# Vcc.net
KiCad netlist of a schematic drawn in EAGLE
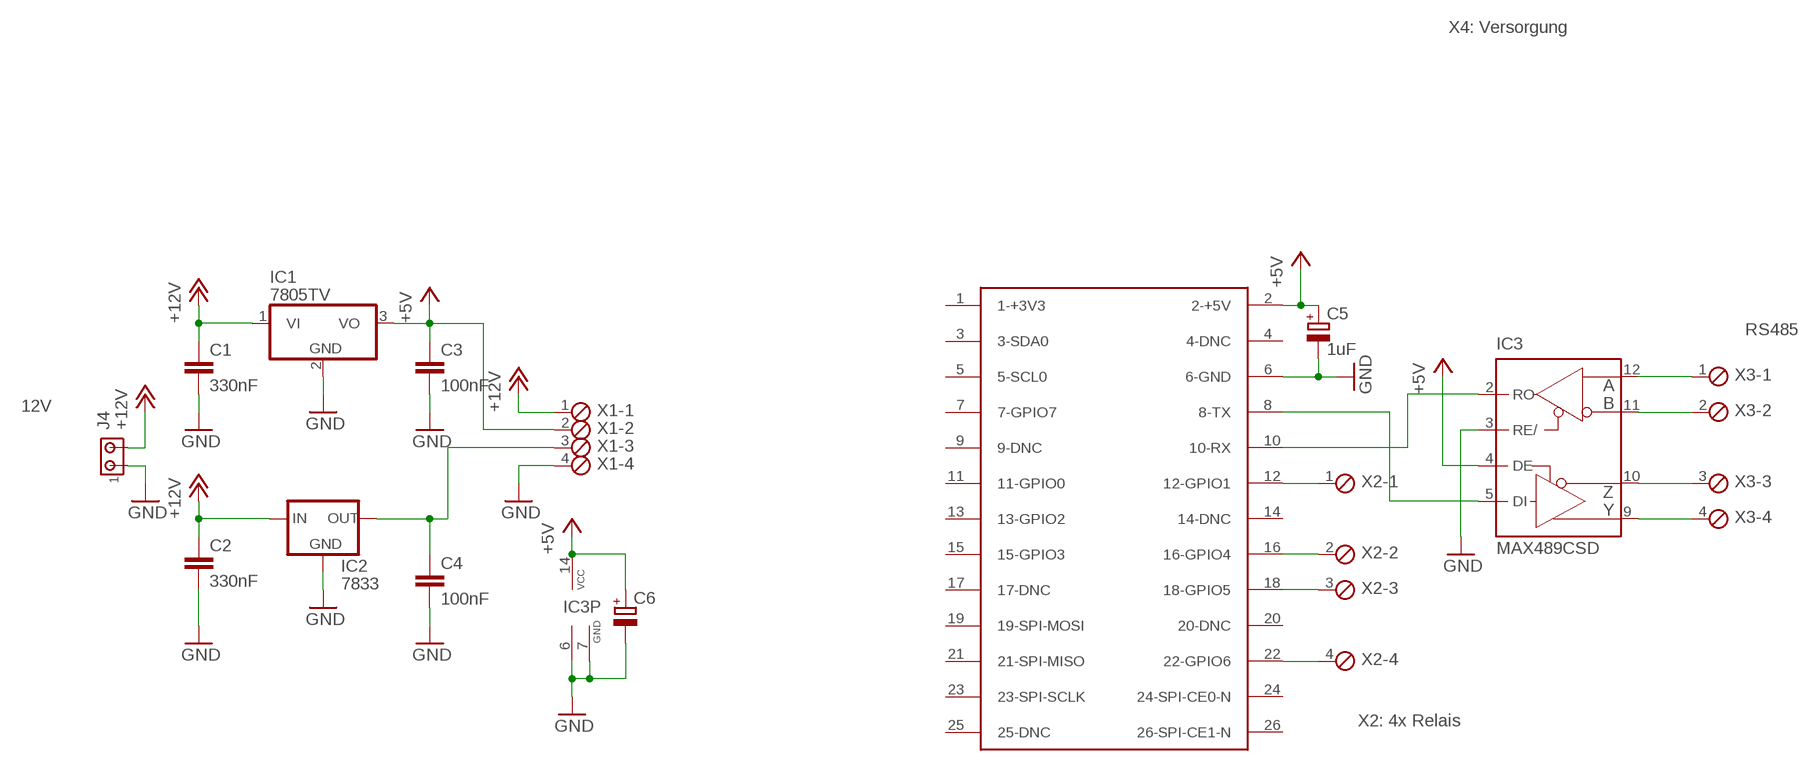
[diagram p0: schematic, sheet 1]

(export (version "E")
  (design (tool "Eeschema 10.0.6"))
  (components
    (comp (ref "C1")
      (value "330nF")
      (footprint "eagle-import:C050-035X075")
      (libsource (lib "eagle-import") (part "C-EU050-035X075"))
    )
    (comp (ref "C2")
      (value "330nF")
      (footprint "eagle-import:C050-035X075")
      (libsource (lib "eagle-import") (part "C-EU050-035X075"))
    )
    (comp (ref "C3")
      (value "100nF")
      (footprint "eagle-import:C050-035X075")
      (libsource (lib "eagle-import") (part "C-EU050-035X075"))
    )
    (comp (ref "C4")
      (value "100nF")
      (footprint "eagle-import:C050-035X075")
      (libsource (lib "eagle-import") (part "C-EU050-035X075"))
    )
    (comp (ref "C5")
      (value "1uF")
      (footprint "eagle-import:E2,5-7")
      (libsource (lib "eagle-import") (part "CPOL-EUE2.5-7"))
    )
    (comp (ref "C6")
      (value "CPOL-EUE2.5-7")
      (footprint "eagle-import:E2,5-7")
      (libsource (lib "eagle-import") (part "CPOL-EUE2.5-7"))
    )
    (comp (ref "IC1")
      (value "7805TV")
      (footprint "eagle-import:TO220V")
      (libsource (lib "eagle-import") (part "78TV05"))
    )
    (comp (ref "IC2")
      (value "7833")
      (footprint "eagle-import:78XXS")
      (libsource (lib "eagle-import") (part "78XXS"))
    )
    (comp (ref "IC3")
      (value "MAX489CSD")
      (footprint "eagle-import:SO14")
      (fields (field (name "MF") "MAXIM"))
      (libsource (lib "eagle-import") (part "MAX489CSD"))
    )
    (comp (ref "J4")
      (value "MTA02-100")
      (footprint "eagle-import:10X02MTA")
      (libsource (lib "eagle-import") (part "MTA02-100"))
    )
    (comp (ref "U$1")
      (value "RASPBERRY-PI")
      (footprint "eagle-import:RASPBERRY-PI")
      (libsource (lib "eagle-import") (part "RASPBERRY-PI"))
    )
    (comp (ref "X1")
      (value "MPT4")
      (footprint "eagle-import:4POL254")
      (libsource (lib "eagle-import") (part "MPT4"))
    )
    (comp (ref "X2")
      (value "MPT4")
      (footprint "eagle-import:4POL254")
      (libsource (lib "eagle-import") (part "MPT4"))
    )
    (comp (ref "X3")
      (value "MPT4")
      (footprint "eagle-import:4POL254")
      (libsource (lib "eagle-import") (part "MPT4"))
    )
  )
  (nets
    (net (code "1") (name "+5V") (class "Default")
      (node (ref "C3") (pin "1") (pinfunction "1_1") (pintype "passive"))
      (node (ref "C5") (pin "+") (pinfunction "+_+") (pintype "passive"))
      (node (ref "C6") (pin "+") (pinfunction "+_+") (pintype "passive"))
      (node (ref "IC1") (pin "3") (pinfunction "VO_3") (pintype "passive"))
      (node (ref "IC3") (pin "14") (pinfunction "VCC_14") (pintype "power_in"))
      (node (ref "IC3") (pin "4") (pinfunction "DE_4") (pintype "input"))
      (node (ref "U$1") (pin "2") (pinfunction "2-+5V_2") (pintype "bidirectional"))
      (node (ref "X1") (pin "2") (pinfunction "1_2") (pintype "passive"))
    )
    (net (code "2") (name "+12V") (class "Default")
      (node (ref "C1") (pin "1") (pinfunction "1_1") (pintype "passive"))
      (node (ref "C2") (pin "1") (pinfunction "1_1") (pintype "passive"))
      (node (ref "IC1") (pin "1") (pinfunction "VI_1") (pintype "input"))
      (node (ref "IC2") (pin "IN") (pinfunction "IN_IN") (pintype "input"))
      (node (ref "J4") (pin "2") (pinfunction "2_2") (pintype "passive"))
      (node (ref "X1") (pin "1") (pinfunction "1_1") (pintype "passive"))
    )
    (net (code "3") (name "GND") (class "Default")
      (node (ref "C1") (pin "2") (pinfunction "2_2") (pintype "passive"))
      (node (ref "C2") (pin "2") (pinfunction "2_2") (pintype "passive"))
      (node (ref "C3") (pin "2") (pinfunction "2_2") (pintype "passive"))
      (node (ref "C4") (pin "2") (pinfunction "2_2") (pintype "passive"))
      (node (ref "C5") (pin "-") (pinfunction "-_-") (pintype "passive"))
      (node (ref "C6") (pin "-") (pinfunction "-_-") (pintype "passive"))
      (node (ref "IC1") (pin "2") (pinfunction "GND_2") (pintype "passive"))
      (node (ref "IC2") (pin "GND") (pinfunction "GND_GND") (pintype "input"))
      (node (ref "IC3") (pin "3") (pinfunction "RE/_3") (pintype "input"))
      (node (ref "IC3") (pin "6") (pinfunction "GND_6") (pintype "power_in"))
      (node (ref "IC3") (pin "7") (pinfunction "GND_7") (pintype "power_in"))
      (node (ref "J4") (pin "1") (pinfunction "1_1") (pintype "passive"))
      (node (ref "U$1") (pin "6") (pinfunction "6-GND_6") (pintype "bidirectional"))
      (node (ref "X1") (pin "4") (pinfunction "1_4") (pintype "passive"))
    )
    (net (code "4") (name "Net-(IC3D-A)") (class "Default")
      (node (ref "IC3") (pin "12") (pinfunction "A_12") (pintype "passive"))
      (node (ref "X3") (pin "1") (pinfunction "1_1") (pintype "passive"))
    )
    (net (code "5") (name "Net-(IC3D-B)") (class "Default")
      (node (ref "IC3") (pin "11") (pinfunction "B_11") (pintype "passive"))
      (node (ref "X3") (pin "2") (pinfunction "1_2") (pintype "passive"))
    )
    (net (code "6") (name "Net-(IC3D-DI)") (class "Default")
      (node (ref "IC3") (pin "5") (pinfunction "DI_5") (pintype "input"))
      (node (ref "U$1") (pin "8") (pinfunction "8-TX_8") (pintype "bidirectional"))
    )
    (net (code "7") (name "Net-(IC3D-RO)") (class "Default")
      (node (ref "IC3") (pin "2") (pinfunction "RO_2") (pintype "output"))
      (node (ref "U$1") (pin "10") (pinfunction "10-RX_10") (pintype "bidirectional"))
    )
    (net (code "8") (name "Net-(IC3D-Y)") (class "Default")
      (node (ref "IC3") (pin "9") (pinfunction "Y_9") (pintype "passive"))
      (node (ref "X3") (pin "4") (pinfunction "1_4") (pintype "passive"))
    )
    (net (code "9") (name "Net-(IC3D-Z)") (class "Default")
      (node (ref "IC3") (pin "10") (pinfunction "Z_10") (pintype "passive"))
      (node (ref "X3") (pin "3") (pinfunction "1_3") (pintype "passive"))
    )
    (net (code "10") (name "Net-(U$1-12-GPIO1)") (class "Default")
      (node (ref "U$1") (pin "12") (pinfunction "12-GPIO1_12") (pintype "bidirectional"))
      (node (ref "X2") (pin "1") (pinfunction "1_1") (pintype "passive"))
    )
    (net (code "11") (name "Net-(U$1-16-GPIO4)") (class "Default")
      (node (ref "U$1") (pin "16") (pinfunction "16-GPIO4_16") (pintype "bidirectional"))
      (node (ref "X2") (pin "2") (pinfunction "1_2") (pintype "passive"))
    )
    (net (code "12") (name "Net-(U$1-18-GPIO5)") (class "Default")
      (node (ref "U$1") (pin "18") (pinfunction "18-GPIO5_18") (pintype "bidirectional"))
      (node (ref "X2") (pin "3") (pinfunction "1_3") (pintype "passive"))
    )
    (net (code "13") (name "Net-(U$1-22-GPIO6)") (class "Default")
      (node (ref "U$1") (pin "22") (pinfunction "22-GPIO6_22") (pintype "bidirectional"))
      (node (ref "X2") (pin "4") (pinfunction "1_4") (pintype "passive"))
    )
    (net (code "14") (name "Net-(X1C-1)") (class "Default")
      (node (ref "C4") (pin "1") (pinfunction "1_1") (pintype "passive"))
      (node (ref "IC2") (pin "OUT") (pinfunction "OUT_OUT") (pintype "passive"))
      (node (ref "X1") (pin "3") (pinfunction "1_3") (pintype "passive"))
    )
    (net (code "15") (name "unconnected-(U$1-1-+3V3-Pad1)") (class "Default")
      (node (ref "U$1") (pin "1") (pinfunction "1-+3V3_1") (pintype "bidirectional"))
    )
    (net (code "16") (name "unconnected-(U$1-3-SDA0-Pad3)") (class "Default")
      (node (ref "U$1") (pin "3") (pinfunction "3-SDA0_3") (pintype "bidirectional"))
    )
    (net (code "17") (name "unconnected-(U$1-4-DNC-Pad4)") (class "Default")
      (node (ref "U$1") (pin "4") (pinfunction "4-DNC_4") (pintype "bidirectional"))
    )
    (net (code "18") (name "unconnected-(U$1-5-SCL0-Pad5)") (class "Default")
      (node (ref "U$1") (pin "5") (pinfunction "5-SCL0_5") (pintype "bidirectional"))
    )
    (net (code "19") (name "unconnected-(U$1-7-GPIO7-Pad7)") (class "Default")
      (node (ref "U$1") (pin "7") (pinfunction "7-GPIO7_7") (pintype "bidirectional"))
    )
    (net (code "20") (name "unconnected-(U$1-9-DNC-Pad9)") (class "Default")
      (node (ref "U$1") (pin "9") (pinfunction "9-DNC_9") (pintype "bidirectional"))
    )
    (net (code "21") (name "unconnected-(U$1-11-GPIO0-Pad11)") (class "Default")
      (node (ref "U$1") (pin "11") (pinfunction "11-GPIO0_11") (pintype "bidirectional"))
    )
    (net (code "22") (name "unconnected-(U$1-13-GPIO2-Pad13)") (class "Default")
      (node (ref "U$1") (pin "13") (pinfunction "13-GPIO2_13") (pintype "bidirectional"))
    )
    (net (code "23") (name "unconnected-(U$1-14-DNC-Pad14)") (class "Default")
      (node (ref "U$1") (pin "14") (pinfunction "14-DNC_14") (pintype "bidirectional"))
    )
    (net (code "24") (name "unconnected-(U$1-15-GPIO3-Pad15)") (class "Default")
      (node (ref "U$1") (pin "15") (pinfunction "15-GPIO3_15") (pintype "bidirectional"))
    )
    (net (code "25") (name "unconnected-(U$1-17-DNC-Pad17)") (class "Default")
      (node (ref "U$1") (pin "17") (pinfunction "17-DNC_17") (pintype "bidirectional"))
    )
    (net (code "26") (name "unconnected-(U$1-19-SPI-MOSI-Pad19)") (class "Default")
      (node (ref "U$1") (pin "19") (pinfunction "19-SPI-MOSI_19") (pintype "bidirectional"))
    )
    (net (code "27") (name "unconnected-(U$1-20-DNC-Pad20)") (class "Default")
      (node (ref "U$1") (pin "20") (pinfunction "20-DNC_20") (pintype "bidirectional"))
    )
    (net (code "28") (name "unconnected-(U$1-21-SPI-MISO-Pad21)") (class "Default")
      (node (ref "U$1") (pin "21") (pinfunction "21-SPI-MISO_21") (pintype "bidirectional"))
    )
    (net (code "29") (name "unconnected-(U$1-23-SPI-SCLK-Pad23)") (class "Default")
      (node (ref "U$1") (pin "23") (pinfunction "23-SPI-SCLK_23") (pintype "bidirectional"))
    )
    (net (code "30") (name "unconnected-(U$1-24-SPI-CE0-N-Pad24)") (class "Default")
      (node (ref "U$1") (pin "24") (pinfunction "24-SPI-CE0-N_24") (pintype "bidirectional"))
    )
    (net (code "31") (name "unconnected-(U$1-25-DNC-Pad25)") (class "Default")
      (node (ref "U$1") (pin "25") (pinfunction "25-DNC_25") (pintype "bidirectional"))
    )
    (net (code "32") (name "unconnected-(U$1-26-SPI-CE1-N-Pad26)") (class "Default")
      (node (ref "U$1") (pin "26") (pinfunction "26-SPI-CE1-N_26") (pintype "bidirectional"))
    )
  )
)
